# IR_BEAT.net
KiCad netlist of a schematic drawn in Altium Designer
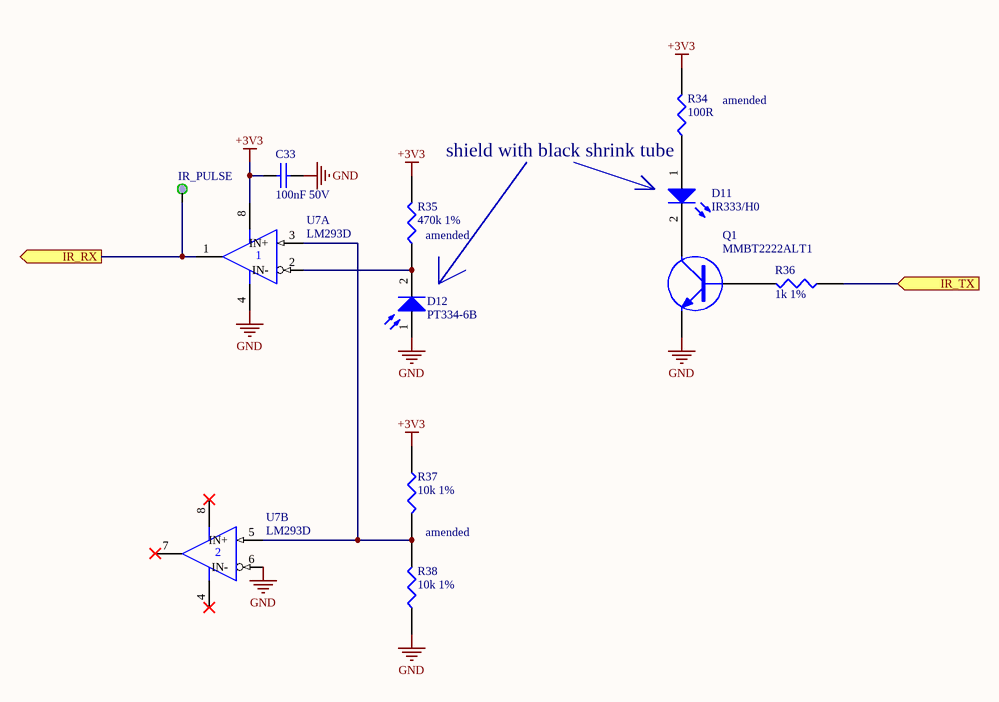
[diagram p0: IR_BEAT.SchDoc]

(export (version "E")
  (design (tool "Eeschema 10.0.6"))
  (components
    (comp (ref "C33")
      (value "100nF 50V")
      (footprint "IPC-7352 Chip_Capacitor_N:CAPC2012N")
      (description "Capacitor")
      (libsource (lib "*") (part "CAP"))
    )
    (comp (ref "D11")
      (value "IR333/H0")
      (footprint "UserPcbLib:LED5.08/2.54-2")
      (description "Typical INFRARED GaAs LED")
      (fields (field (name "MANUFACTURER") "Everlight"))
      (libsource (lib "Miscellaneous Devices") (part "LED0"))
    )
    (comp (ref "D12")
      (value "PT334-6B")
      (footprint "UserPcbLib:LED5.08/2.54-2")
      (description "Photosensitive Diode")
      (fields (field (name "MANUFACTURER") "Everlight"))
      (libsource (lib "Miscellaneous Devices") (part "Photo Sen"))
    )
    (comp (ref "IR_PULSE")
      (value "IR PULSE")
      (footprint "UserPcbLib:TP1.4/1.0")
      (libsource (lib "UserSchlib") (part "TP1.4/1.0"))
    )
    (comp (ref "Q1")
      (value "MMBT2222ALT1")
      (footprint "SOT23_N:SOT23-3N")
      (description "NPN transistor")
      (libsource (lib "*") (part "MMBT3904"))
    )
    (comp (ref "R34")
      (value "100R")
      (footprint "IPC-7352 Chip_Resistor_N:RESC2012N")
      (libsource (lib "*") (part "RES1"))
    )
    (comp (ref "R35")
      (value "470k 1%")
      (footprint "IPC-7352 Chip_Resistor_N:RESC2012N")
      (libsource (lib "*") (part "RES1"))
    )
    (comp (ref "R36")
      (value "1k 1%")
      (footprint "IPC-7352 Chip_Resistor_N:RESC2012N")
      (libsource (lib "*") (part "RES1"))
    )
    (comp (ref "R37")
      (value "10k 1%")
      (footprint "IPC-7352 Chip_Resistor_N:RESC2012N")
      (libsource (lib "*") (part "RES1"))
    )
    (comp (ref "R38")
      (value "10k 1%")
      (footprint "IPC-7352 Chip_Resistor_N:RESC2012N")
      (libsource (lib "*") (part "RES1"))
    )
    (comp (ref "U7")
      (value "LM293D")
      (footprint "ST-Microelectronics Footprints:SOP8_M")
      (description "Dual Differential Comparator")
      (fields (field (name "PUBLISHER") "Altium Limited"))
      (libsource (lib "TI Logic Comparator") (part "LM393D"))
    )
  )
  (nets
    (net (code "1") (name "+3V3") (class "Default")
      (node (ref "C33") (pin "2") (pinfunction "2_2") (pintype "passive"))
      (node (ref "R34") (pin "2") (pinfunction "2_2") (pintype "passive"))
      (node (ref "R35") (pin "2") (pinfunction "2_2") (pintype "passive"))
      (node (ref "R37") (pin "1") (pinfunction "1_1") (pintype "passive"))
      (node (ref "U7") (pin "8") (pinfunction "VCC_8") (pintype "power_in"))
    )
    (net (code "2") (name "/IR_RX") (class "Default")
      (node (ref "IR_PULSE") (pin "1") (pinfunction "1_1") (pintype "passive"))
      (node (ref "U7") (pin "1") (pinfunction "OUT_1") (pintype "open_collector"))
    )
    (net (code "3") (name "/IR_TX") (class "Default")
      (node (ref "R36") (pin "1") (pinfunction "1_1") (pintype "passive"))
    )
    (net (code "4") (name "GND") (class "Default")
      (node (ref "C33") (pin "1") (pinfunction "1_1") (pintype "passive"))
      (node (ref "D12") (pin "1") (pinfunction "A_1") (pintype "passive"))
      (node (ref "Q1") (pin "2") (pinfunction "E_2") (pintype "passive"))
      (node (ref "R38") (pin "1") (pinfunction "1_1") (pintype "passive"))
      (node (ref "U7") (pin "4") (pinfunction "GND_4") (pintype "power_in"))
      (node (ref "U7") (pin "6") (pinfunction "IN-_6") (pintype "input"))
    )
    (net (code "5") (name "Net-(D11-A)") (class "Default")
      (node (ref "D11") (pin "1") (pinfunction "A_1") (pintype "passive"))
      (node (ref "R34") (pin "1") (pinfunction "1_1") (pintype "passive"))
    )
    (net (code "6") (name "Net-(D11-K)") (class "Default")
      (node (ref "D11") (pin "2") (pinfunction "K_2") (pintype "passive"))
      (node (ref "Q1") (pin "3") (pinfunction "C_3") (pintype "passive"))
    )
    (net (code "7") (name "Net-(D12-K)") (class "Default")
      (node (ref "D12") (pin "2") (pinfunction "K_2") (pintype "passive"))
      (node (ref "R35") (pin "1") (pinfunction "1_1") (pintype "passive"))
      (node (ref "U7") (pin "2") (pinfunction "IN-_2") (pintype "input"))
    )
    (net (code "8") (name "Net-(Q1-B)") (class "Default")
      (node (ref "Q1") (pin "1") (pinfunction "B_1") (pintype "passive"))
      (node (ref "R36") (pin "2") (pinfunction "2_2") (pintype "passive"))
    )
    (net (code "9") (name "Net-(U7A-IN+)") (class "Default")
      (node (ref "R37") (pin "2") (pinfunction "2_2") (pintype "passive"))
      (node (ref "R38") (pin "2") (pinfunction "2_2") (pintype "passive"))
      (node (ref "U7") (pin "3") (pinfunction "IN+_3") (pintype "input"))
      (node (ref "U7") (pin "5") (pinfunction "IN+_5") (pintype "input"))
    )
    (net (code "10") (name "unconnected-(U7B-GND-Pad4)") (class "Default")
      (node (ref "U7") (pin "4") (pinfunction "GND_4") (pintype "power_in+no_connect"))
    )
    (net (code "11") (name "unconnected-(U7B-OUT-Pad7)") (class "Default")
      (node (ref "U7") (pin "7") (pinfunction "OUT_7") (pintype "open_collector+no_connect"))
    )
    (net (code "12") (name "unconnected-(U7B-VCC-Pad8)") (class "Default")
      (node (ref "U7") (pin "8") (pinfunction "VCC_8") (pintype "power_in+no_connect"))
    )
  )
)
